# LPDDR4X_other.net
KiCad netlist of a schematic drawn in Altium Designer
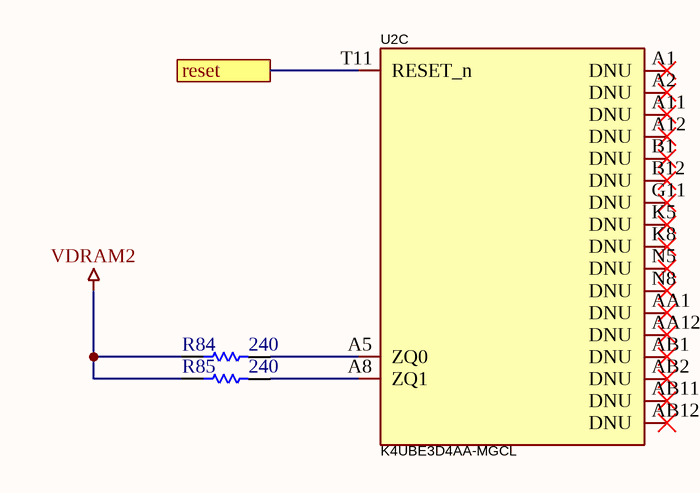
[diagram p0: LPDDR4X_other.SchDoc]

(export (version "E")
  (design (tool "Eeschema 10.0.6"))
  (components
    (comp (ref "R84")
      (value "240")
      (footprint "R0603")
      (fields (field (name "Comment") "R0603"))
      (libsource (lib "kit") (part "R0603"))
    )
    (comp (ref "R85")
      (value "240")
      (footprint "R0603")
      (fields (field (name "Comment") "R0603"))
      (libsource (lib "kit") (part "R0603"))
    )
    (comp (ref "U2")
      (value "K4UBE3D4AA-MGCL")
      (footprint "K4F8E304HB-MGCJ")
      (fields (field (name "MANUFACTURER") "SAMSUNG(三星半导体)"))
      (libsource (lib "kit") (part "K4UBE3D4AA-MGCL"))
    )
  )
  (nets
    (net (code "1") (name "/reset") (class "Default")
      (node (ref "U2") (pin "T11") (pinfunction "RESET_n_T11") (pintype "passive"))
    )
    (net (code "2") (name "Net-(U2C-ZQ0)") (class "Default")
      (node (ref "R84") (pin "2") (pinfunction "2_2") (pintype "passive"))
      (node (ref "U2") (pin "A5") (pinfunction "ZQ0_A5") (pintype "passive"))
    )
    (net (code "3") (name "Net-(U2C-ZQ1)") (class "Default")
      (node (ref "R85") (pin "2") (pinfunction "2_2") (pintype "passive"))
      (node (ref "U2") (pin "A8") (pinfunction "ZQ1_A8") (pintype "passive"))
    )
    (net (code "4") (name "VDRAM2") (class "Default")
      (node (ref "R84") (pin "1") (pinfunction "1_1") (pintype "passive"))
      (node (ref "R85") (pin "1") (pinfunction "1_1") (pintype "passive"))
    )
    (net (code "5") (name "unconnected-(U2C-DNU-PadA1)") (class "Default")
      (node (ref "U2") (pin "A1") (pinfunction "DNU_A1") (pintype "passive+no_connect"))
    )
    (net (code "6") (name "unconnected-(U2C-DNU-PadA2)") (class "Default")
      (node (ref "U2") (pin "A2") (pinfunction "DNU_A2") (pintype "passive+no_connect"))
    )
    (net (code "7") (name "unconnected-(U2C-DNU-PadA11)") (class "Default")
      (node (ref "U2") (pin "A11") (pinfunction "DNU_A11") (pintype "passive+no_connect"))
    )
    (net (code "8") (name "unconnected-(U2C-DNU-PadA12)") (class "Default")
      (node (ref "U2") (pin "A12") (pinfunction "DNU_A12") (pintype "passive+no_connect"))
    )
    (net (code "9") (name "unconnected-(U2C-DNU-PadAA1)") (class "Default")
      (node (ref "U2") (pin "AA1") (pinfunction "DNU_AA1") (pintype "passive+no_connect"))
    )
    (net (code "10") (name "unconnected-(U2C-DNU-PadAA12)") (class "Default")
      (node (ref "U2") (pin "AA12") (pinfunction "DNU_AA12") (pintype "passive+no_connect"))
    )
    (net (code "11") (name "unconnected-(U2C-DNU-PadAB1)") (class "Default")
      (node (ref "U2") (pin "AB1") (pinfunction "DNU_AB1") (pintype "passive+no_connect"))
    )
    (net (code "12") (name "unconnected-(U2C-DNU-PadAB2)") (class "Default")
      (node (ref "U2") (pin "AB2") (pinfunction "DNU_AB2") (pintype "passive+no_connect"))
    )
    (net (code "13") (name "unconnected-(U2C-DNU-PadAB11)") (class "Default")
      (node (ref "U2") (pin "AB11") (pinfunction "DNU_AB11") (pintype "passive+no_connect"))
    )
    (net (code "14") (name "unconnected-(U2C-DNU-PadAB12)") (class "Default")
      (node (ref "U2") (pin "AB12") (pinfunction "DNU_AB12") (pintype "passive+no_connect"))
    )
    (net (code "15") (name "unconnected-(U2C-DNU-PadB1)") (class "Default")
      (node (ref "U2") (pin "B1") (pinfunction "DNU_B1") (pintype "passive+no_connect"))
    )
    (net (code "16") (name "unconnected-(U2C-DNU-PadB12)") (class "Default")
      (node (ref "U2") (pin "B12") (pinfunction "DNU_B12") (pintype "passive+no_connect"))
    )
    (net (code "17") (name "unconnected-(U2C-DNU-PadG11)") (class "Default")
      (node (ref "U2") (pin "G11") (pinfunction "DNU_G11") (pintype "passive+no_connect"))
    )
    (net (code "18") (name "unconnected-(U2C-DNU-PadK5)") (class "Default")
      (node (ref "U2") (pin "K5") (pinfunction "DNU_K5") (pintype "passive+no_connect"))
    )
    (net (code "19") (name "unconnected-(U2C-DNU-PadK8)") (class "Default")
      (node (ref "U2") (pin "K8") (pinfunction "DNU_K8") (pintype "passive+no_connect"))
    )
    (net (code "20") (name "unconnected-(U2C-DNU-PadN5)") (class "Default")
      (node (ref "U2") (pin "N5") (pinfunction "DNU_N5") (pintype "passive+no_connect"))
    )
    (net (code "21") (name "unconnected-(U2C-DNU-PadN8)") (class "Default")
      (node (ref "U2") (pin "N8") (pinfunction "DNU_N8") (pintype "passive+no_connect"))
    )
  )
)
